# eeprom.net
KiCad netlist of a schematic drawn in EAGLE
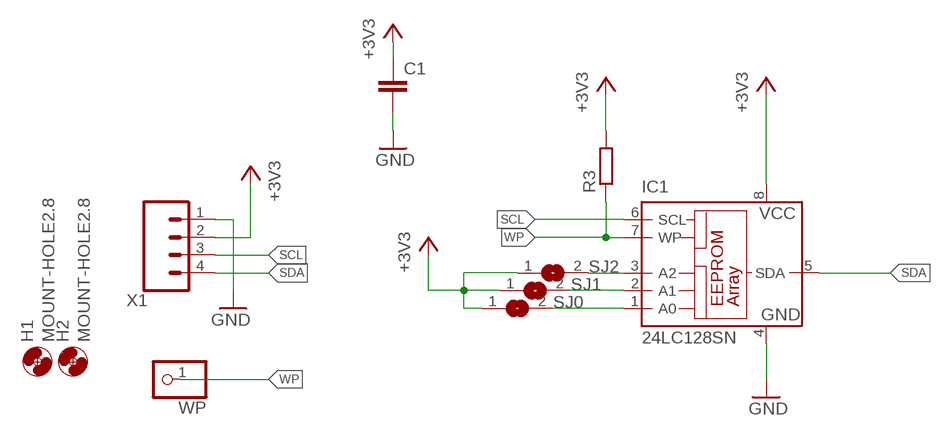
[diagram p0: schematic, sheet 1]

(export (version "E")
  (design (tool "Eeschema 10.0.6"))
  (components
    (comp (ref "C1")
      (value "C-EUC0805")
      (footprint "eagle-import:C0805")
      (libsource (lib "eagle-import") (part "C-EUC0805"))
    )
    (comp (ref "H1")
      (value "MOUNT-HOLE2.8")
      (footprint "eagle-import:2,8")
      (libsource (lib "eagle-import") (part "MOUNT-HOLE2.8"))
    )
    (comp (ref "H2")
      (value "MOUNT-HOLE2.8")
      (footprint "eagle-import:2,8")
      (libsource (lib "eagle-import") (part "MOUNT-HOLE2.8"))
    )
    (comp (ref "IC1")
      (value "24LC128SN")
      (footprint "eagle-import:SO-08")
      (fields (field (name "MF") "MICROCHIP") (field (name "MPN") "24LC128-I/SNG"))
      (libsource (lib "eagle-import") (part "24SNLC128"))
    )
    (comp (ref "R3")
      (value "R-EU_R0805")
      (footprint "eagle-import:R0805")
      (libsource (lib "eagle-import") (part "R-EU_R0805"))
    )
    (comp (ref "SJ0") (value "SJ") (footprint "eagle-import:SJ") (libsource (lib "eagle-import") (part "SJ")))
    (comp (ref "SJ1") (value "SJ") (footprint "eagle-import:SJ") (libsource (lib "eagle-import") (part "SJ")))
    (comp (ref "SJ2") (value "SJ") (footprint "eagle-import:SJ") (libsource (lib "eagle-import") (part "SJ")))
    (comp (ref "WP")
      (value "PINHD-1X1")
      (footprint "eagle-import:1X01")
      (libsource (lib "eagle-import") (part "PINHD-1X1"))
    )
    (comp (ref "X1")
      (value "JST-XH-04-PIN-ROUND-PAD")
      (footprint "eagle-import:JST-XH-04-PACKAGE-ROUND-PAD")
      (libsource (lib "eagle-import") (part "JST-XH-04-PIN-ROUND-PAD"))
    )
  )
  (nets
    (net (code "1") (name "+3V3") (class "Default")
      (node (ref "C1") (pin "1") (pinfunction "1_1") (pintype "passive"))
      (node (ref "IC1") (pin "8") (pinfunction "VCC_8") (pintype "power_in"))
      (node (ref "R3") (pin "2") (pinfunction "2_2") (pintype "passive"))
      (node (ref "SJ0") (pin "1") (pinfunction "1_1") (pintype "passive"))
      (node (ref "SJ1") (pin "1") (pinfunction "1_1") (pintype "passive"))
      (node (ref "SJ2") (pin "1") (pinfunction "1_1") (pintype "passive"))
      (node (ref "X1") (pin "2") (pinfunction "2_2") (pintype "passive"))
    )
    (net (code "2") (name "GND") (class "Default")
      (node (ref "C1") (pin "2") (pinfunction "2_2") (pintype "passive"))
      (node (ref "IC1") (pin "4") (pinfunction "GND_4") (pintype "power_in"))
      (node (ref "X1") (pin "1") (pinfunction "1_1") (pintype "passive"))
    )
    (net (code "3") (name "Net-(IC1-A0)") (class "Default")
      (node (ref "IC1") (pin "1") (pinfunction "A0_1") (pintype "input"))
      (node (ref "SJ0") (pin "2") (pinfunction "2_2") (pintype "passive"))
    )
    (net (code "4") (name "Net-(IC1-A1)") (class "Default")
      (node (ref "IC1") (pin "2") (pinfunction "A1_2") (pintype "input"))
      (node (ref "SJ1") (pin "2") (pinfunction "2_2") (pintype "passive"))
    )
    (net (code "5") (name "Net-(IC1-A2)") (class "Default")
      (node (ref "IC1") (pin "3") (pinfunction "A2_3") (pintype "input"))
      (node (ref "SJ2") (pin "2") (pinfunction "2_2") (pintype "passive"))
    )
    (net (code "6") (name "SCL") (class "Default")
      (node (ref "IC1") (pin "6") (pinfunction "SCL_6") (pintype "input"))
      (node (ref "X1") (pin "3") (pinfunction "3_3") (pintype "passive"))
    )
    (net (code "7") (name "SDA") (class "Default")
      (node (ref "IC1") (pin "5") (pinfunction "SDA_5") (pintype "bidirectional"))
      (node (ref "X1") (pin "4") (pinfunction "4_4") (pintype "passive"))
    )
    (net (code "8") (name "WP") (class "Default")
      (node (ref "IC1") (pin "7") (pinfunction "WP_7") (pintype "input"))
      (node (ref "R3") (pin "1") (pinfunction "1_1") (pintype "passive"))
      (node (ref "WP") (pin "1") (pinfunction "1_1") (pintype "passive"))
    )
  )
)
